# PWR_MCU.net
KiCad netlist of a schematic drawn in Altium Designer
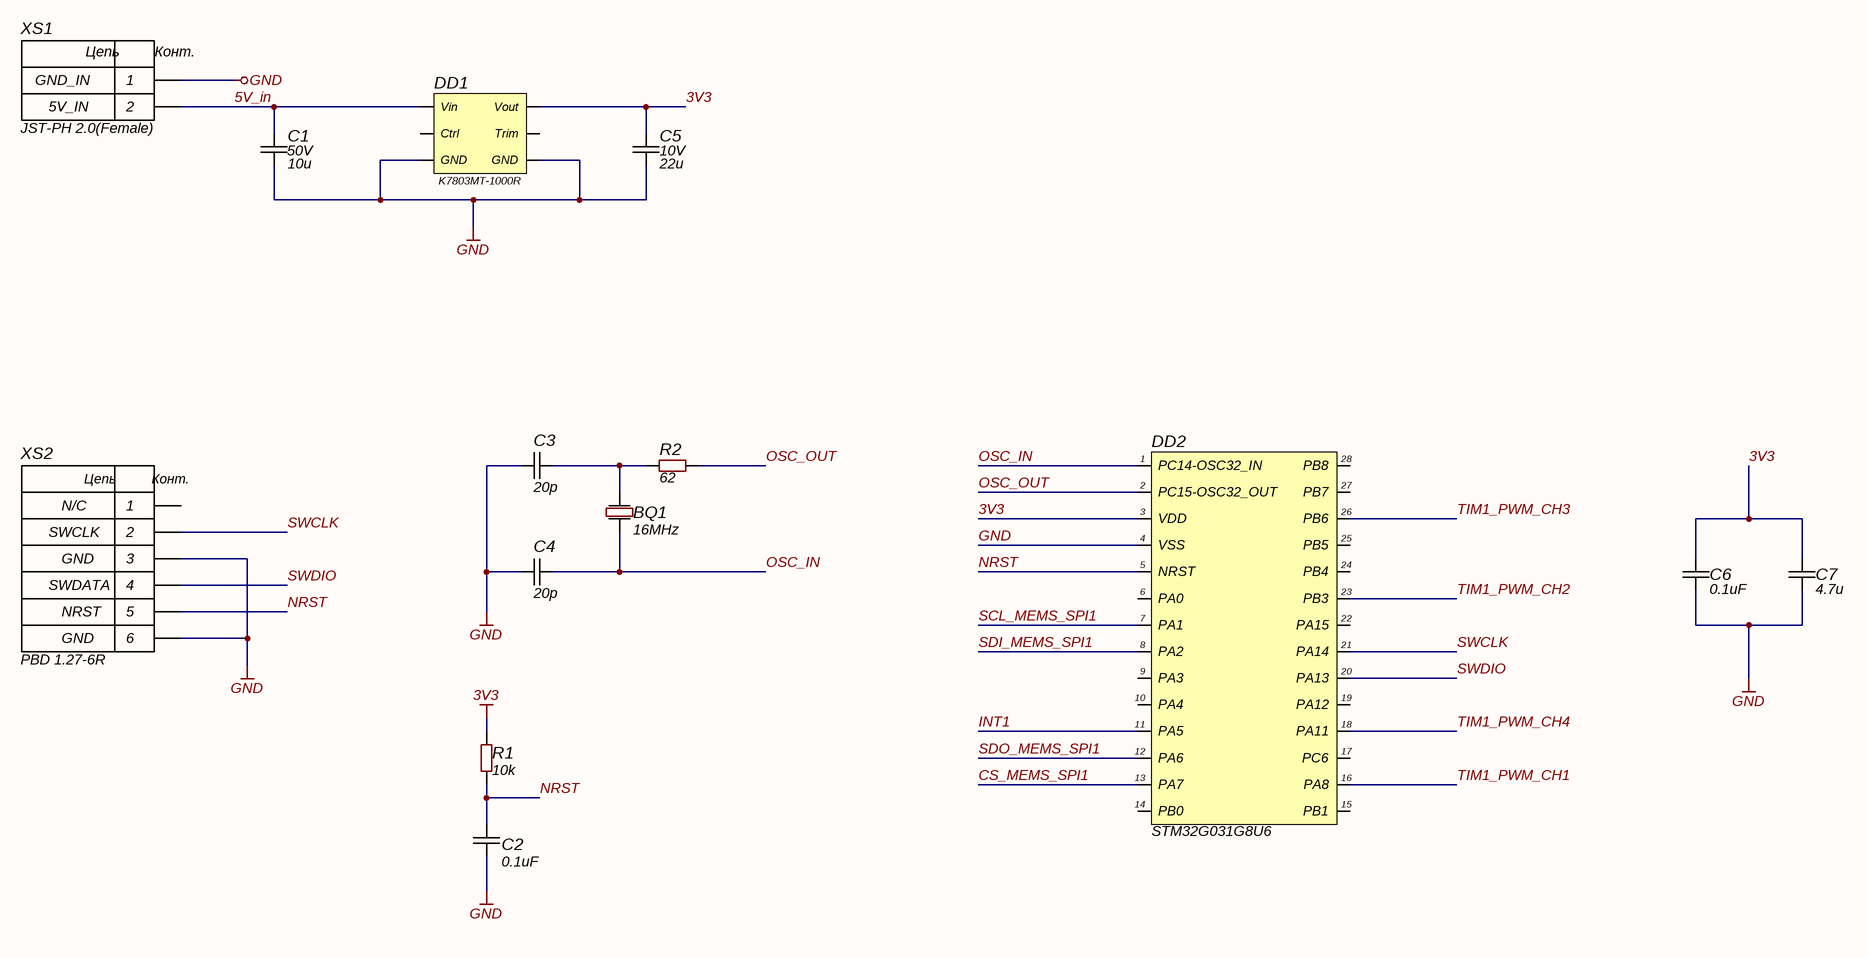
[diagram p0: PWR_MCU.SchDoc]

(export (version "E")
  (design (tool "Eeschema 10.0.6"))
  (components
    (comp (ref "BQ1")
      (value "SMD3225-16.000MHz")
      (footprint "OSC: 3225")
      (description "Resonator")
      (fields
        (field (name "MANUFACTURER") "Diodes Incorporated")
        (field (name "PARTNUMBER") "FL1000002")
        (field (name "FREQUENCY") "16MHz")
      )
      (libsource (lib "oscilator") (part "Crystal_3225"))
    )
    (comp (ref "C1")
      (value "10u")
      (footprint "CAP: 1206")
      (fields
        (field (name "MANUFACTURER") "Yageo")
        (field (name "PARTNUMBER") "CC1206KRX7R9BB104")
        (field (name "VALUEMANUFACTURERPARTNUMBER") "Ceramic capacitor, 10u, X7R, ±10%, 50V, 1206, -55...+125°C")
        (field (name "VOLTAGE") "50V")
      )
      (libsource (lib "capacitor") (part "Ceramic_1206"))
    )
    (comp (ref "C2")
      (value "0.1uF")
      (footprint "CAP: 0603")
      (fields
        (field (name "MANUFACTURER") "Yageo")
        (field (name "PARTNUMBER") "CC0603KRX7R7BB104")
        (field (name "VALUEMANUFACTURERPARTNUMBER") "Ceramic capacitor, 0.1uF, X7R, ±10%, 16V, 0603, -55...+125°C")
      )
      (libsource (lib "capacitor") (part "Ceramic_0603"))
    )
    (comp (ref "C3")
      (value "20p")
      (footprint "CAP: 0603")
      (description "Capacitor")
      (fields (field (name "MANUFACTURER") "Yageo") (field (name "PARTNUMBER") "CC0603KRX7R7BB104"))
      (libsource (lib "capacitor") (part "Ceramic_0603"))
    )
    (comp (ref "C4")
      (value "20p")
      (footprint "CAP: 0603")
      (description "Capacitor")
      (fields (field (name "MANUFACTURER") "Yageo") (field (name "PARTNUMBER") "CC0603KRX7R7BB104"))
      (libsource (lib "capacitor") (part "Ceramic_0603"))
    )
    (comp (ref "C5")
      (value "22u")
      (footprint "CAP: 0603")
      (description "Capacitor")
      (fields
        (field (name "MANUFACTURER") "Yageo")
        (field (name "PARTNUMBER") "CC0603KRX7R7BB104")
        (field (name "VOLTAGE") "10V")
      )
      (libsource (lib "capacitor") (part "Ceramic_0603"))
    )
    (comp (ref "C6")
      (value "0.1uF")
      (footprint "CAP: 0603")
      (fields
        (field (name "MANUFACTURER") "Yageo")
        (field (name "PARTNUMBER") "CC0603KRX7R7BB104")
        (field (name "VALUEMANUFACTURERPARTNUMBER") "Ceramic capacitor, 0.1uF, X7R, ±10%, 16V, 0603, -55...+125°C")
      )
      (libsource (lib "capacitor") (part "Ceramic_0603"))
    )
    (comp (ref "C7")
      (value "4.7u")
      (footprint "CAP: 0603")
      (fields
        (field (name "MANUFACTURER") "Yageo")
        (field (name "PARTNUMBER") "CC0603KRX7R7BB104")
        (field (name "VALUEMANUFACTURERPARTNUMBER") "Ceramic capacitor, 4.7u, X7R, ±10%, 16V, 0603, -55...+125°C")
      )
      (libsource (lib "capacitor") (part "Ceramic_0603"))
    )
    (comp (ref "DD1")
      (value "K7803MT-1000R")
      (footprint "DFN_K7805")
      (description "DC/DC converter")
      (libsource (lib "ic-power-supply") (part "K7805MT-500R"))
    )
    (comp (ref "DD2")
      (value "STM32G031G8U6")
      (footprint "28-UFQFPN")
      (description "Cortex-M0+")
      (libsource (lib "ic-mcu") (part "STM32G031G8U6"))
    )
    (comp (ref "R1")
      (value "10k")
      (footprint "RES: 0603")
      (fields
        (field (name "MANUFACTURER") "Yageo")
        (field (name "PARTNUMBER") "RC0603JR-07100RL")
        (field (name "VALUEMANUFACTURERPARTNUMBER") "Resistor film, 10k, , 0603, 0.1W, -55...+125°C")
      )
      (libsource (lib "resistor") (part "Resistor_0603"))
    )
    (comp (ref "R2")
      (value "62")
      (footprint "RES: 0603")
      (description "Resistor")
      (fields (field (name "MANUFACTURER") "Yageo") (field (name "PARTNUMBER") "RC0603JR-07100RL"))
      (libsource (lib "") (part "Resistor_0603_1"))
    )
    (comp (ref "XS1")
      (value "JST-PH 2.0(Female)")
      (footprint "JST-PH 2.0(Female)")
      (libsource (lib "connector") (part "JST-PH 2.0(Female)"))
    )
    (comp (ref "XS2")
      (value "PBD 1.27-6R")
      (footprint "CON: PLLD-6R(1.27)")
      (description "DS1065-14-2X3S8BR")
      (libsource (lib "connector") (part "PBD 1.27-6R"))
    )
  )
  (nets
    (net (code "1") (name "/5V_in") (class "Default")
      (node (ref "C1") (pin "2") (pinfunction "2_2") (pintype "passive"))
      (node (ref "DD1") (pin "1") (pinfunction "Vin_1") (pintype "passive"))
      (node (ref "XS1") (pin "2") (pinfunction "2_2") (pintype "passive"))
    )
    (net (code "2") (name "/CS_MEMS_SPI1") (class "Default")
      (node (ref "DD2") (pin "13") (pinfunction "PA7_13") (pintype "passive"))
    )
    (net (code "3") (name "/INT1") (class "Default")
      (node (ref "DD2") (pin "11") (pinfunction "PA5_11") (pintype "passive"))
    )
    (net (code "4") (name "/NRST") (class "Default")
      (node (ref "C2") (pin "2") (pinfunction "2_2") (pintype "passive"))
      (node (ref "DD2") (pin "5") (pinfunction "NRST_5") (pintype "passive"))
      (node (ref "R1") (pin "1") (pinfunction "1_1") (pintype "passive"))
      (node (ref "XS2") (pin "5") (pinfunction "5_5") (pintype "passive"))
    )
    (net (code "5") (name "/OSC_IN") (class "Default")
      (node (ref "BQ1") (pin "1") (pinfunction "1_1") (pintype "passive"))
      (node (ref "C4") (pin "1") (pinfunction "1_1") (pintype "passive"))
      (node (ref "DD2") (pin "1") (pinfunction "PC14-OSC32_IN_1") (pintype "passive"))
    )
    (net (code "6") (name "/OSC_OUT") (class "Default")
      (node (ref "DD2") (pin "2") (pinfunction "PC15-OSC32_OUT_2") (pintype "passive"))
      (node (ref "R2") (pin "1") (pinfunction "1_1") (pintype "passive"))
    )
    (net (code "7") (name "/SCL_MEMS_SPI1") (class "Default")
      (node (ref "DD2") (pin "7") (pinfunction "PA1_7") (pintype "passive"))
    )
    (net (code "8") (name "/SDI_MEMS_SPI1") (class "Default")
      (node (ref "DD2") (pin "8") (pinfunction "PA2_8") (pintype "passive"))
    )
    (net (code "9") (name "/SDO_MEMS_SPI1") (class "Default")
      (node (ref "DD2") (pin "12") (pinfunction "PA6_12") (pintype "passive"))
    )
    (net (code "10") (name "/SWCLK") (class "Default")
      (node (ref "DD2") (pin "21") (pinfunction "PA14_21") (pintype "passive"))
      (node (ref "XS2") (pin "2") (pinfunction "2_2") (pintype "passive"))
    )
    (net (code "11") (name "/SWDIO") (class "Default")
      (node (ref "DD2") (pin "20") (pinfunction "PA13_20") (pintype "passive"))
      (node (ref "XS2") (pin "4") (pinfunction "4_4") (pintype "passive"))
    )
    (net (code "12") (name "/TIM1_PWM_CH1") (class "Default")
      (node (ref "DD2") (pin "16") (pinfunction "PA8_16") (pintype "passive"))
    )
    (net (code "13") (name "/TIM1_PWM_CH2") (class "Default")
      (node (ref "DD2") (pin "23") (pinfunction "PB3_23") (pintype "passive"))
    )
    (net (code "14") (name "/TIM1_PWM_CH3") (class "Default")
      (node (ref "DD2") (pin "26") (pinfunction "PB6_26") (pintype "passive"))
    )
    (net (code "15") (name "/TIM1_PWM_CH4") (class "Default")
      (node (ref "DD2") (pin "18") (pinfunction "PA11_18") (pintype "passive"))
    )
    (net (code "16") (name "3V3") (class "Default")
      (node (ref "C5") (pin "2") (pinfunction "2_2") (pintype "passive"))
      (node (ref "C6") (pin "2") (pinfunction "2_2") (pintype "passive"))
      (node (ref "C7") (pin "2") (pinfunction "2_2") (pintype "passive"))
      (node (ref "DD1") (pin "3") (pinfunction "Vout_3") (pintype "passive"))
      (node (ref "DD2") (pin "3") (pinfunction "VDD_3") (pintype "passive"))
      (node (ref "R1") (pin "2") (pinfunction "2_2") (pintype "passive"))
    )
    (net (code "17") (name "GND") (class "Default")
      (node (ref "C1") (pin "1") (pinfunction "1_1") (pintype "passive"))
      (node (ref "C2") (pin "1") (pinfunction "1_1") (pintype "passive"))
      (node (ref "C3") (pin "2") (pinfunction "2_2") (pintype "passive"))
      (node (ref "C4") (pin "2") (pinfunction "2_2") (pintype "passive"))
      (node (ref "C5") (pin "1") (pinfunction "1_1") (pintype "passive"))
      (node (ref "C6") (pin "1") (pinfunction "1_1") (pintype "passive"))
      (node (ref "C7") (pin "1") (pinfunction "1_1") (pintype "passive"))
      (node (ref "DD1") (pin "2") (pinfunction "GND_2") (pintype "passive"))
      (node (ref "DD1") (pin "5") (pinfunction "GND_5") (pintype "passive"))
      (node (ref "DD2") (pin "4") (pinfunction "VSS_4") (pintype "passive"))
      (node (ref "XS1") (pin "1") (pinfunction "1_1") (pintype "passive"))
      (node (ref "XS2") (pin "3") (pinfunction "3_3") (pintype "passive"))
      (node (ref "XS2") (pin "6") (pinfunction "6_6") (pintype "passive"))
    )
    (net (code "18") (name "Net-(BQ1-Pad3)") (class "Default")
      (node (ref "BQ1") (pin "3") (pinfunction "3_3") (pintype "passive"))
      (node (ref "C3") (pin "1") (pinfunction "1_1") (pintype "passive"))
      (node (ref "R2") (pin "2") (pinfunction "2_2") (pintype "passive"))
    )
    (net (code "19") (name "unconnected-(DD1-Ctrl-Pad6)") (class "Default")
      (node (ref "DD1") (pin "6") (pinfunction "Ctrl_6") (pintype "passive"))
    )
    (net (code "20") (name "unconnected-(DD1-Trim-Pad4)") (class "Default")
      (node (ref "DD1") (pin "4") (pinfunction "Trim_4") (pintype "passive"))
    )
    (net (code "21") (name "unconnected-(DD2-PA0-Pad6)") (class "Default")
      (node (ref "DD2") (pin "6") (pinfunction "PA0_6") (pintype "passive"))
    )
    (net (code "22") (name "unconnected-(DD2-PA3-Pad9)") (class "Default")
      (node (ref "DD2") (pin "9") (pinfunction "PA3_9") (pintype "passive"))
    )
    (net (code "23") (name "unconnected-(DD2-PA4-Pad10)") (class "Default")
      (node (ref "DD2") (pin "10") (pinfunction "PA4_10") (pintype "passive"))
    )
    (net (code "24") (name "unconnected-(DD2-PA12-Pad19)") (class "Default")
      (node (ref "DD2") (pin "19") (pinfunction "PA12_19") (pintype "passive"))
    )
    (net (code "25") (name "unconnected-(DD2-PA15-Pad22)") (class "Default")
      (node (ref "DD2") (pin "22") (pinfunction "PA15_22") (pintype "passive"))
    )
    (net (code "26") (name "unconnected-(DD2-PB0-Pad14)") (class "Default")
      (node (ref "DD2") (pin "14") (pinfunction "PB0_14") (pintype "passive"))
    )
    (net (code "27") (name "unconnected-(DD2-PB1-Pad15)") (class "Default")
      (node (ref "DD2") (pin "15") (pinfunction "PB1_15") (pintype "passive"))
    )
    (net (code "28") (name "unconnected-(DD2-PB4-Pad24)") (class "Default")
      (node (ref "DD2") (pin "24") (pinfunction "PB4_24") (pintype "passive"))
    )
    (net (code "29") (name "unconnected-(DD2-PB5-Pad25)") (class "Default")
      (node (ref "DD2") (pin "25") (pinfunction "PB5_25") (pintype "passive"))
    )
    (net (code "30") (name "unconnected-(DD2-PB7-Pad27)") (class "Default")
      (node (ref "DD2") (pin "27") (pinfunction "PB7_27") (pintype "passive"))
    )
    (net (code "31") (name "unconnected-(DD2-PB8-Pad28)") (class "Default")
      (node (ref "DD2") (pin "28") (pinfunction "PB8_28") (pintype "passive"))
    )
    (net (code "32") (name "unconnected-(DD2-PC6-Pad17)") (class "Default")
      (node (ref "DD2") (pin "17") (pinfunction "PC6_17") (pintype "passive"))
    )
    (net (code "33") (name "unconnected-(XS2-Pad1)") (class "Default")
      (node (ref "XS2") (pin "1") (pinfunction "1_1") (pintype "passive"))
    )
  )
)
